# rgb2scart.net
KiCad netlist of a schematic drawn in EAGLE
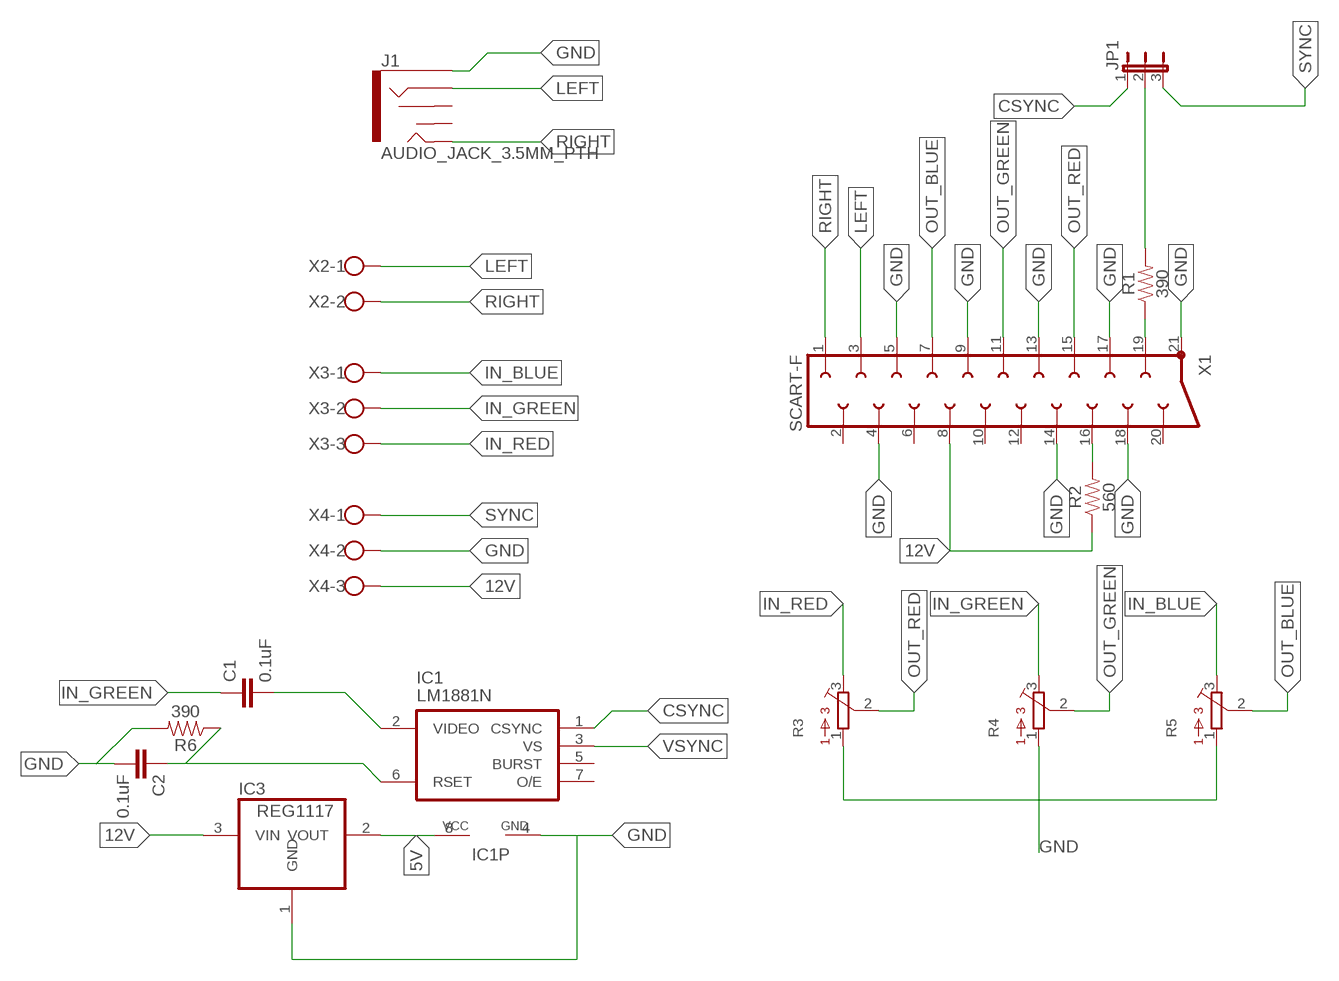
[diagram p0: schematic, sheet 1]

(export (version "E")
  (design (tool "Eeschema 10.0.6"))
  (components
    (comp (ref "C1")
      (value "0.1uF")
      (footprint "eagle-import:CAP-PTH-SMALL-KIT")
      (libsource (lib "eagle-import") (part "0.1UF-KIT-EZ-50V-20%"))
    )
    (comp (ref "C2")
      (value "0.1uF")
      (footprint "eagle-import:CAP-PTH-SMALL-KIT")
      (libsource (lib "eagle-import") (part "0.1UF-KIT-EZ-50V-20%"))
    )
    (comp (ref "IC1")
      (value "LM1881N")
      (footprint "eagle-import:DIL08")
      (libsource (lib "eagle-import") (part "LM1881N"))
    )
    (comp (ref "IC3")
      (value "REG1117")
      (footprint "eagle-import:SOT223")
      (libsource (lib "eagle-import") (part "REG1117"))
    )
    (comp (ref "J1")
      (value "AUDIO_JACK_3.5MM_PTH")
      (footprint "eagle-import:AUDIO-JACK")
      (libsource (lib "eagle-import") (part "AUDIO_JACK_3.5MM_PTH"))
    )
    (comp (ref "JP1")
      (value "JP2E")
      (footprint "eagle-import:JP2")
      (libsource (lib "eagle-import") (part "JP2E"))
    )
    (comp (ref "R1")
      (value "390")
      (footprint "eagle-import:AXIAL-0.3")
      (libsource (lib "eagle-import") (part "1KOHM-HORIZ-1/4W-1%"))
    )
    (comp (ref "R2")
      (value "560")
      (footprint "eagle-import:AXIAL-0.3")
      (libsource (lib "eagle-import") (part "1KOHM-HORIZ-1/4W-1%"))
    )
    (comp (ref "R3")
      (value "3362P")
      (footprint "eagle-import:3362P")
      (libsource (lib "eagle-import") (part "3362P"))
    )
    (comp (ref "R4")
      (value "3362P")
      (footprint "eagle-import:3362P")
      (libsource (lib "eagle-import") (part "3362P"))
    )
    (comp (ref "R5")
      (value "3362P")
      (footprint "eagle-import:3362P")
      (libsource (lib "eagle-import") (part "3362P"))
    )
    (comp (ref "R6")
      (value "390")
      (footprint "eagle-import:AXIAL-0.3")
      (libsource (lib "eagle-import") (part "1KOHM-HORIZ-1/4W-1%"))
    )
    (comp (ref "X1")
      (value "SCART-F")
      (footprint "eagle-import:SCART-F")
      (libsource (lib "eagle-import") (part "SCART-F"))
    )
    (comp (ref "X2")
      (value "W237-102")
      (footprint "eagle-import:W237-102")
      (fields (field (name "MPN") "237-102"))
      (libsource (lib "eagle-import") (part "W237-102"))
    )
    (comp (ref "X3")
      (value "W237-103")
      (footprint "eagle-import:W237-103")
      (fields (field (name "MPN") "237-103"))
      (libsource (lib "eagle-import") (part "W237-103"))
    )
    (comp (ref "X4")
      (value "W237-103")
      (footprint "eagle-import:W237-103")
      (fields (field (name "MPN") "237-103"))
      (libsource (lib "eagle-import") (part "W237-103"))
    )
  )
  (nets
    (net (code "1") (name "5V") (class "Default")
      (node (ref "IC1") (pin "8") (pinfunction "VCC_8") (pintype "power_in"))
      (node (ref "IC3") (pin "2") (pinfunction "VOUT_2") (pintype "output"))
    )
    (net (code "2") (name "12V") (class "Default")
      (node (ref "IC3") (pin "3") (pinfunction "VIN_3") (pintype "input"))
      (node (ref "R2") (pin "P$1") (pinfunction "1_P$1") (pintype "passive"))
      (node (ref "X1") (pin "8") (pinfunction "8_8") (pintype "passive"))
      (node (ref "X4") (pin "3") (pinfunction "KL_3") (pintype "passive"))
    )
    (net (code "3") (name "CSYNC") (class "Default")
      (node (ref "IC1") (pin "1") (pinfunction "CSYNC_1") (pintype "output"))
      (node (ref "JP1") (pin "1") (pinfunction "1_1") (pintype "passive"))
    )
    (net (code "4") (name "GND") (class "Default")
      (node (ref "C2") (pin "2") (pinfunction "2_2") (pintype "passive"))
      (node (ref "IC1") (pin "4") (pinfunction "GND_4") (pintype "power_in"))
      (node (ref "IC3") (pin "1") (pinfunction "GND_1") (pintype "power_in"))
      (node (ref "J1") (pin "SLEEVE") (pinfunction "SLEEVE_SLEEVE") (pintype "bidirectional"))
      (node (ref "R3") (pin "1") (pinfunction "1_1") (pintype "passive"))
      (node (ref "R4") (pin "1") (pinfunction "1_1") (pintype "passive"))
      (node (ref "R5") (pin "1") (pinfunction "1_1") (pintype "passive"))
      (node (ref "R6") (pin "P$2") (pinfunction "2_P$2") (pintype "passive"))
      (node (ref "X1") (pin "13") (pinfunction "13_13") (pintype "passive"))
      (node (ref "X1") (pin "14") (pinfunction "14_14") (pintype "passive"))
      (node (ref "X1") (pin "17") (pinfunction "17_17") (pintype "passive"))
      (node (ref "X1") (pin "18") (pinfunction "18_18") (pintype "passive"))
      (node (ref "X1") (pin "21") (pinfunction "21_21") (pintype "passive"))
      (node (ref "X1") (pin "4") (pinfunction "4_4") (pintype "passive"))
      (node (ref "X1") (pin "5") (pinfunction "5_5") (pintype "passive"))
      (node (ref "X1") (pin "9") (pinfunction "9_9") (pintype "passive"))
      (node (ref "X4") (pin "2") (pinfunction "KL_2") (pintype "passive"))
    )
    (net (code "5") (name "IN_BLUE") (class "Default")
      (node (ref "R5") (pin "3") (pinfunction "3_3") (pintype "passive"))
      (node (ref "X3") (pin "1") (pinfunction "KL_1") (pintype "passive"))
    )
    (net (code "6") (name "IN_GREEN") (class "Default")
      (node (ref "C1") (pin "1") (pinfunction "1_1") (pintype "passive"))
      (node (ref "R4") (pin "3") (pinfunction "3_3") (pintype "passive"))
      (node (ref "X3") (pin "2") (pinfunction "KL_2") (pintype "passive"))
    )
    (net (code "7") (name "IN_RED") (class "Default")
      (node (ref "R3") (pin "3") (pinfunction "3_3") (pintype "passive"))
      (node (ref "X3") (pin "3") (pinfunction "KL_3") (pintype "passive"))
    )
    (net (code "8") (name "LEFT") (class "Default")
      (node (ref "J1") (pin "RING") (pinfunction "RING_RING") (pintype "bidirectional"))
      (node (ref "X1") (pin "3") (pinfunction "3_3") (pintype "passive"))
      (node (ref "X2") (pin "1") (pinfunction "KL_1") (pintype "passive"))
    )
    (net (code "9") (name "Net-(IC1A-RSET)") (class "Default")
      (node (ref "C2") (pin "1") (pinfunction "1_1") (pintype "passive"))
      (node (ref "IC1") (pin "6") (pinfunction "RSET_6") (pintype "passive"))
      (node (ref "R6") (pin "P$1") (pinfunction "1_P$1") (pintype "passive"))
    )
    (net (code "10") (name "Net-(IC1A-VIDEO)") (class "Default")
      (node (ref "C1") (pin "2") (pinfunction "2_2") (pintype "passive"))
      (node (ref "IC1") (pin "2") (pinfunction "VIDEO_2") (pintype "input"))
    )
    (net (code "11") (name "Net-(R1-1)") (class "Default")
      (node (ref "R1") (pin "P$1") (pinfunction "1_P$1") (pintype "passive"))
      (node (ref "X1") (pin "19") (pinfunction "19_19") (pintype "passive"))
    )
    (net (code "12") (name "Net-(R1-2)") (class "Default")
      (node (ref "JP1") (pin "2") (pinfunction "2_2") (pintype "passive"))
      (node (ref "R1") (pin "P$2") (pinfunction "2_P$2") (pintype "passive"))
    )
    (net (code "13") (name "Net-(R2-2)") (class "Default")
      (node (ref "R2") (pin "P$2") (pinfunction "2_P$2") (pintype "passive"))
      (node (ref "X1") (pin "16") (pinfunction "16_16") (pintype "passive"))
    )
    (net (code "14") (name "OUT_BLUE") (class "Default")
      (node (ref "R5") (pin "2") (pinfunction "2_2") (pintype "passive"))
      (node (ref "X1") (pin "7") (pinfunction "7_7") (pintype "passive"))
    )
    (net (code "15") (name "OUT_GREEN") (class "Default")
      (node (ref "R4") (pin "2") (pinfunction "2_2") (pintype "passive"))
      (node (ref "X1") (pin "11") (pinfunction "11_11") (pintype "passive"))
    )
    (net (code "16") (name "OUT_RED") (class "Default")
      (node (ref "R3") (pin "2") (pinfunction "2_2") (pintype "passive"))
      (node (ref "X1") (pin "15") (pinfunction "15_15") (pintype "passive"))
    )
    (net (code "17") (name "RIGHT") (class "Default")
      (node (ref "J1") (pin "TIP") (pinfunction "TIP_TIP") (pintype "bidirectional"))
      (node (ref "X1") (pin "1") (pinfunction "1_1") (pintype "passive"))
      (node (ref "X2") (pin "2") (pinfunction "KL_2") (pintype "passive"))
    )
    (net (code "18") (name "SYNC") (class "Default")
      (node (ref "JP1") (pin "3") (pinfunction "3_3") (pintype "passive"))
      (node (ref "X4") (pin "1") (pinfunction "KL_1") (pintype "passive"))
    )
    (net (code "19") (name "VSYNC") (class "Default")
      (node (ref "IC1") (pin "3") (pinfunction "VS_3") (pintype "output"))
    )
    (net (code "20") (name "unconnected-(IC1A-BURST-Pad5)") (class "Default")
      (node (ref "IC1") (pin "5") (pinfunction "BURST_5") (pintype "output"))
    )
    (net (code "21") (name "unconnected-(IC1A-O{slash}E-Pad7)") (class "Default")
      (node (ref "IC1") (pin "7") (pinfunction "O/E_7") (pintype "output"))
    )
    (net (code "22") (name "unconnected-(J1-PadRSH)") (class "Default")
      (node (ref "J1") (pin "RSH") (pinfunction "RSH_RSH") (pintype "bidirectional"))
    )
    (net (code "23") (name "unconnected-(J1-PadTSH)") (class "Default")
      (node (ref "J1") (pin "TSH") (pinfunction "TSH_TSH") (pintype "bidirectional"))
    )
    (net (code "24") (name "unconnected-(X1-Pad2)") (class "Default")
      (node (ref "X1") (pin "2") (pinfunction "2_2") (pintype "passive"))
    )
    (net (code "25") (name "unconnected-(X1-Pad6)") (class "Default")
      (node (ref "X1") (pin "6") (pinfunction "6_6") (pintype "passive"))
    )
    (net (code "26") (name "unconnected-(X1-Pad10)") (class "Default")
      (node (ref "X1") (pin "10") (pinfunction "10_10") (pintype "passive"))
    )
    (net (code "27") (name "unconnected-(X1-Pad12)") (class "Default")
      (node (ref "X1") (pin "12") (pinfunction "12_12") (pintype "passive"))
    )
    (net (code "28") (name "unconnected-(X1-Pad20)") (class "Default")
      (node (ref "X1") (pin "20") (pinfunction "20_20") (pintype "passive"))
    )
  )
)
